# 16197_4.net
KiCad netlist of a schematic drawn in EAGLE
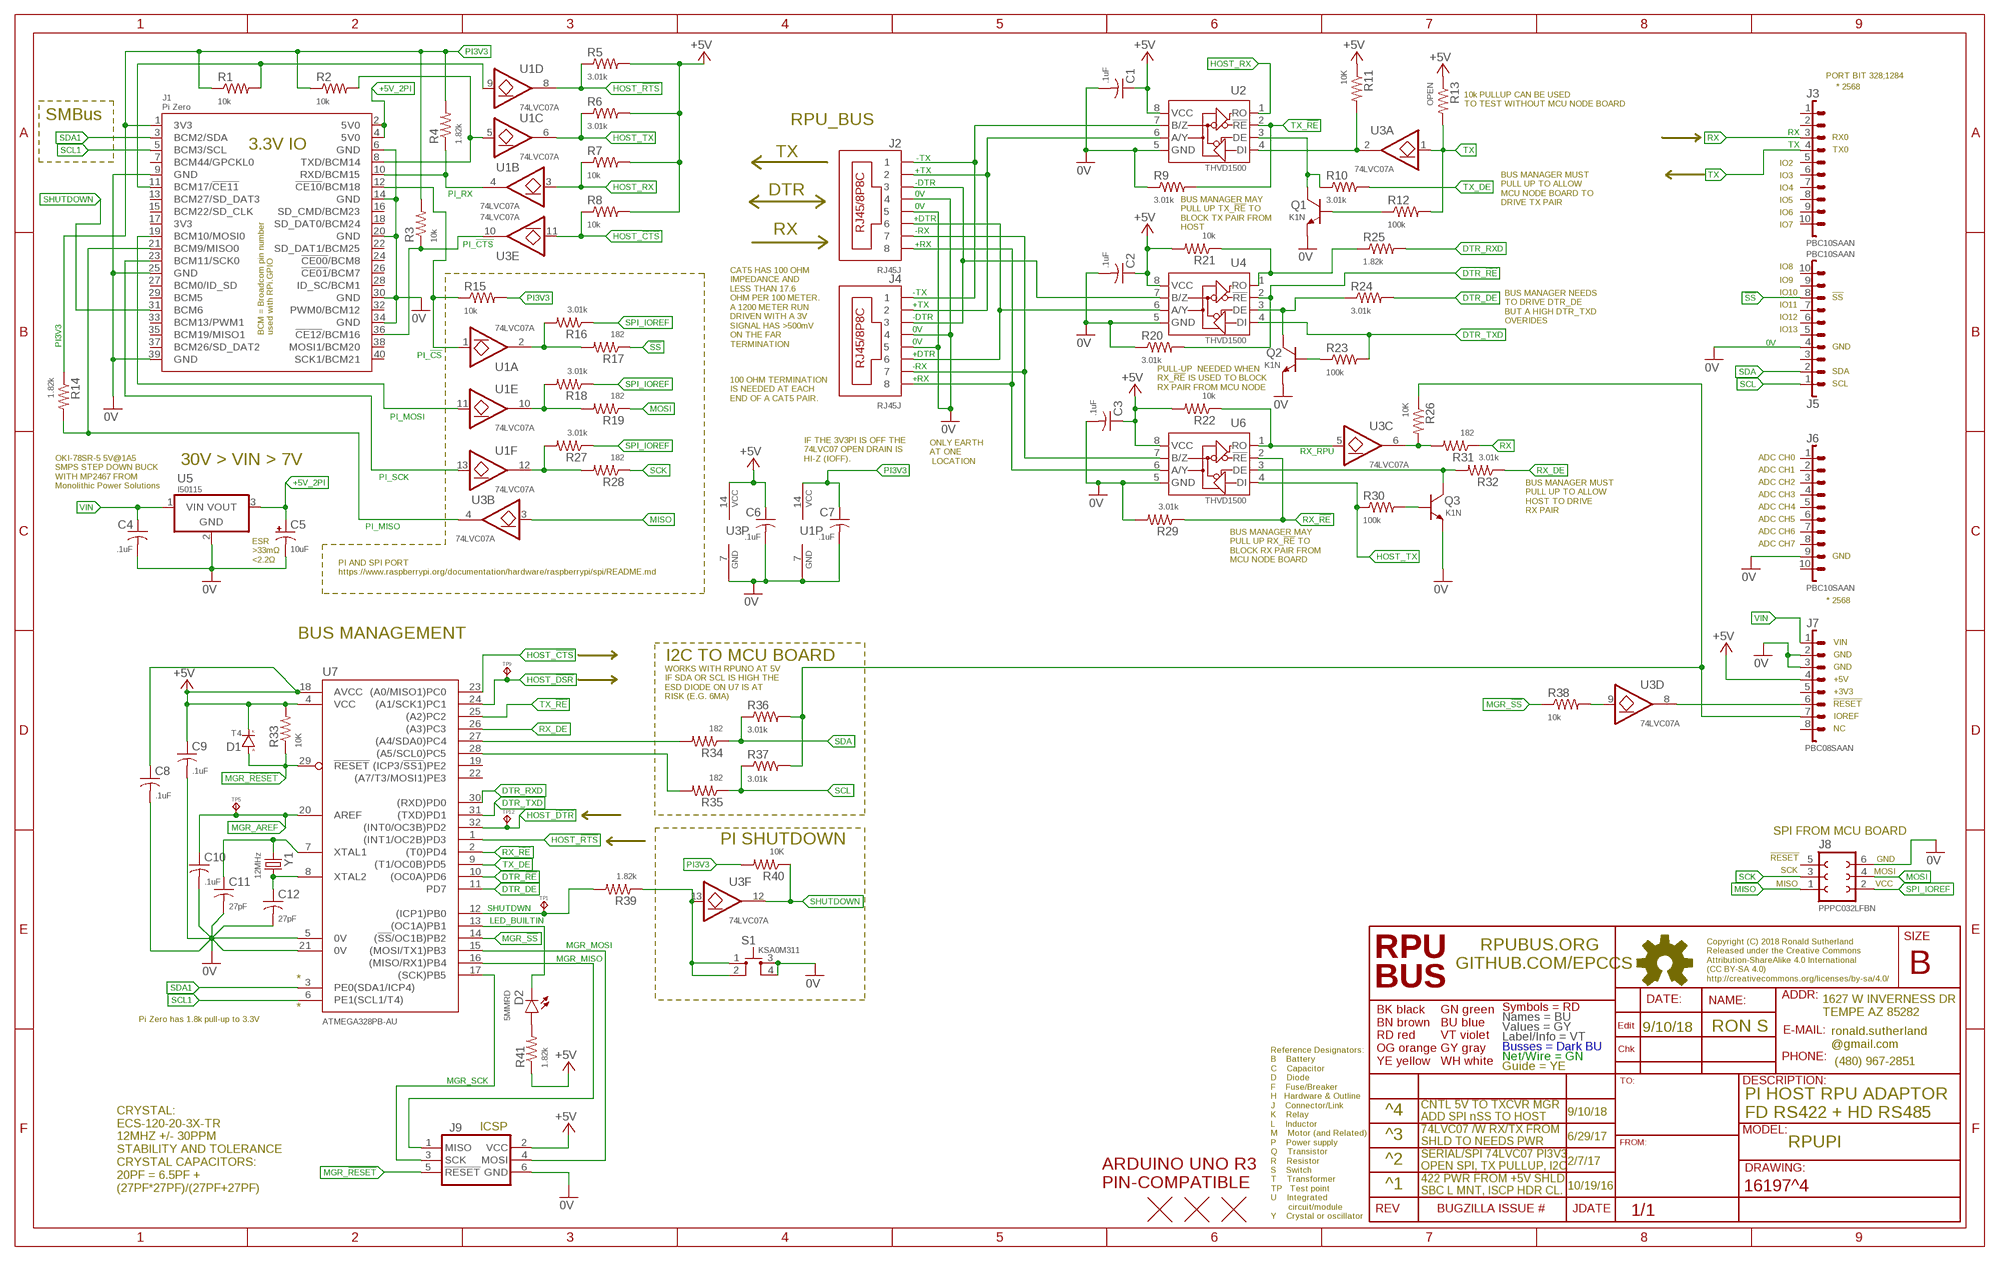
[diagram p0: schematic, sheet 1]

(export (version "E")
  (design (tool "Eeschema 10.0.6"))
  (components
    (comp (ref "C1")
      (value ".1uF")
      (footprint "eagle-import:C0603(1608)")
      (libsource (lib "eagle-import") (part "CC0603A"))
    )
    (comp (ref "C2")
      (value ".1uF")
      (footprint "eagle-import:C0603(1608)")
      (libsource (lib "eagle-import") (part "CC0603A"))
    )
    (comp (ref "C3")
      (value ".1uF")
      (footprint "eagle-import:C0603(1608)")
      (libsource (lib "eagle-import") (part "CC0603A"))
    )
    (comp (ref "C4")
      (value ".1uF")
      (footprint "eagle-import:C0603(1608)")
      (libsource (lib "eagle-import") (part "CC0603A"))
    )
    (comp (ref "C5")
      (value "10uF")
      (footprint "eagle-import:3216")
      (libsource (lib "eagle-import") (part "CT1206"))
    )
    (comp (ref "C6")
      (value ".1uF")
      (footprint "eagle-import:C0603(1608)")
      (libsource (lib "eagle-import") (part "CC0603A"))
    )
    (comp (ref "C7")
      (value ".1uF")
      (footprint "eagle-import:C0603(1608)")
      (libsource (lib "eagle-import") (part "CC0603A"))
    )
    (comp (ref "C8")
      (value ".1uF")
      (footprint "eagle-import:C0603(1608)")
      (libsource (lib "eagle-import") (part "CC0603A"))
    )
    (comp (ref "C9")
      (value ".1uF")
      (footprint "eagle-import:C0603(1608)")
      (libsource (lib "eagle-import") (part "CC0603A"))
    )
    (comp (ref "C10")
      (value ".1uF")
      (footprint "eagle-import:C0603(1608)")
      (libsource (lib "eagle-import") (part "CC0603A"))
    )
    (comp (ref "C11")
      (value "27pF")
      (footprint "eagle-import:C0603(1608)")
      (libsource (lib "eagle-import") (part "CC0603A"))
    )
    (comp (ref "C12")
      (value "27pF")
      (footprint "eagle-import:C0603(1608)")
      (libsource (lib "eagle-import") (part "CC0603A"))
    )
    (comp (ref "D1")
      (value "T4")
      (footprint "eagle-import:SOD123")
      (libsource (lib "eagle-import") (part "DSOD123"))
    )
    (comp (ref "D2")
      (value "5MMRD")
      (footprint "eagle-import:LED5MM")
      (libsource (lib "eagle-import") (part "LED5MM"))
    )
    (comp (ref "J1")
      (value "Pi Zero")
      (footprint "eagle-import:RASPI_ZERO_V40PIN")
      (libsource (lib "eagle-import") (part "RPI-ZERO90"))
    )
    (comp (ref "J2")
      (value "RJ45J")
      (footprint "eagle-import:RJ45-8HZT")
      (libsource (lib "eagle-import") (part "RJ45-8HZT"))
    )
    (comp (ref "J3")
      (value "PBC10SAAN")
      (footprint "eagle-import:1X10")
      (libsource (lib "eagle-import") (part "1X10{dblquote}"))
    )
    (comp (ref "J4")
      (value "RJ45J")
      (footprint "eagle-import:RJ45-8HZT")
      (libsource (lib "eagle-import") (part "RJ45-8HZT"))
    )
    (comp (ref "J5")
      (value "PBC10SAAN")
      (footprint "eagle-import:1X10")
      (libsource (lib "eagle-import") (part "1X10{dblquote}"))
    )
    (comp (ref "J6")
      (value "PBC10SAAN")
      (footprint "eagle-import:1X10")
      (libsource (lib "eagle-import") (part "1X10{dblquote}"))
    )
    (comp (ref "J7")
      (value "PBC08SAAN")
      (footprint "eagle-import:1X8")
      (libsource (lib "eagle-import") (part "1X8{dblquote}"))
    )
    (comp (ref "J8")
      (value "PPPC032LFBN")
      (footprint "eagle-import:F2X3")
      (libsource (lib "eagle-import") (part "F2X3"))
    )
    (comp (ref "J9")
      (value "ISP-SPIPTH")
      (footprint "eagle-import:ISP")
      (libsource (lib "eagle-import") (part "ISP-SPIPTH"))
    )
    (comp (ref "Q1")
      (value "K1N")
      (footprint "eagle-import:SOT23")
      (libsource (lib "eagle-import") (part "NPNSOT23"))
    )
    (comp (ref "Q2")
      (value "K1N")
      (footprint "eagle-import:SOT23")
      (libsource (lib "eagle-import") (part "NPNSOT23"))
    )
    (comp (ref "Q3")
      (value "K1N")
      (footprint "eagle-import:SOT23")
      (libsource (lib "eagle-import") (part "NPNSOT23"))
    )
    (comp (ref "R1")
      (value "10k")
      (footprint "eagle-import:C0805(2012)")
      (libsource (lib "eagle-import") (part "R0805"))
    )
    (comp (ref "R2")
      (value "10k")
      (footprint "eagle-import:C0805(2012)")
      (libsource (lib "eagle-import") (part "R0805"))
    )
    (comp (ref "R3")
      (value "10k")
      (footprint "eagle-import:C0805(2012)")
      (libsource (lib "eagle-import") (part "R0805"))
    )
    (comp (ref "R4")
      (value "1.82k")
      (footprint "eagle-import:C0805(2012)")
      (libsource (lib "eagle-import") (part "R0805"))
    )
    (comp (ref "R5")
      (value "3.01k")
      (footprint "eagle-import:C0805(2012)")
      (libsource (lib "eagle-import") (part "R0805"))
    )
    (comp (ref "R6")
      (value "3.01k")
      (footprint "eagle-import:C0805(2012)")
      (libsource (lib "eagle-import") (part "R0805"))
    )
    (comp (ref "R7")
      (value "10k")
      (footprint "eagle-import:C0805(2012)")
      (libsource (lib "eagle-import") (part "R0805"))
    )
    (comp (ref "R8")
      (value "10k")
      (footprint "eagle-import:C0805(2012)")
      (libsource (lib "eagle-import") (part "R0805"))
    )
    (comp (ref "R9")
      (value "3.01k")
      (footprint "eagle-import:C0805(2012)")
      (libsource (lib "eagle-import") (part "R0805"))
    )
    (comp (ref "R10")
      (value "3.01k")
      (footprint "eagle-import:C0805(2012)")
      (libsource (lib "eagle-import") (part "R0805"))
    )
    (comp (ref "R11")
      (value "10K")
      (footprint "eagle-import:C0805(2012)")
      (libsource (lib "eagle-import") (part "R0805"))
    )
    (comp (ref "R12")
      (value "100k")
      (footprint "eagle-import:C0805(2012)")
      (libsource (lib "eagle-import") (part "R0805"))
    )
    (comp (ref "R13")
      (value "OPEN")
      (footprint "eagle-import:C0805(2012)")
      (libsource (lib "eagle-import") (part "R0805"))
    )
    (comp (ref "R14")
      (value "1.82k")
      (footprint "eagle-import:C0805(2012)")
      (libsource (lib "eagle-import") (part "R0805"))
    )
    (comp (ref "R15")
      (value "10k")
      (footprint "eagle-import:C0805(2012)")
      (libsource (lib "eagle-import") (part "R0805"))
    )
    (comp (ref "R16")
      (value "3.01k")
      (footprint "eagle-import:C0805(2012)")
      (libsource (lib "eagle-import") (part "R0805"))
    )
    (comp (ref "R17")
      (value "182")
      (footprint "eagle-import:C0805(2012)")
      (libsource (lib "eagle-import") (part "R0805"))
    )
    (comp (ref "R18")
      (value "3.01k")
      (footprint "eagle-import:C0805(2012)")
      (libsource (lib "eagle-import") (part "R0805"))
    )
    (comp (ref "R19")
      (value "182")
      (footprint "eagle-import:C0805(2012)")
      (libsource (lib "eagle-import") (part "R0805"))
    )
    (comp (ref "R20")
      (value "3.01k")
      (footprint "eagle-import:C0805(2012)")
      (libsource (lib "eagle-import") (part "R0805"))
    )
    (comp (ref "R21")
      (value "10k")
      (footprint "eagle-import:C0805(2012)")
      (libsource (lib "eagle-import") (part "R0805"))
    )
    (comp (ref "R22")
      (value "10k")
      (footprint "eagle-import:C0805(2012)")
      (libsource (lib "eagle-import") (part "R0805"))
    )
    (comp (ref "R23")
      (value "100k")
      (footprint "eagle-import:C0805(2012)")
      (libsource (lib "eagle-import") (part "R0805"))
    )
    (comp (ref "R24")
      (value "3.01k")
      (footprint "eagle-import:C0805(2012)")
      (libsource (lib "eagle-import") (part "R0805"))
    )
    (comp (ref "R25")
      (value "1.82k")
      (footprint "eagle-import:C0805(2012)")
      (libsource (lib "eagle-import") (part "R0805"))
    )
    (comp (ref "R26")
      (value "10K")
      (footprint "eagle-import:C0805(2012)")
      (libsource (lib "eagle-import") (part "R0805"))
    )
    (comp (ref "R27")
      (value "3.01k")
      (footprint "eagle-import:C0805(2012)")
      (libsource (lib "eagle-import") (part "R0805"))
    )
    (comp (ref "R28")
      (value "182")
      (footprint "eagle-import:C0805(2012)")
      (libsource (lib "eagle-import") (part "R0805"))
    )
    (comp (ref "R29")
      (value "3.01k")
      (footprint "eagle-import:C0805(2012)")
      (libsource (lib "eagle-import") (part "R0805"))
    )
    (comp (ref "R30")
      (value "100k")
      (footprint "eagle-import:C0805(2012)")
      (libsource (lib "eagle-import") (part "R0805"))
    )
    (comp (ref "R31")
      (value "182")
      (footprint "eagle-import:C0805(2012)")
      (libsource (lib "eagle-import") (part "R0805"))
    )
    (comp (ref "R32")
      (value "3.01k")
      (footprint "eagle-import:C0805(2012)")
      (libsource (lib "eagle-import") (part "R0805"))
    )
    (comp (ref "R33")
      (value "10K")
      (footprint "eagle-import:C0805(2012)")
      (libsource (lib "eagle-import") (part "R0805"))
    )
    (comp (ref "R34")
      (value "182")
      (footprint "eagle-import:C0805(2012)")
      (libsource (lib "eagle-import") (part "R0805"))
    )
    (comp (ref "R35")
      (value "182")
      (footprint "eagle-import:C0805(2012)")
      (libsource (lib "eagle-import") (part "R0805"))
    )
    (comp (ref "R36")
      (value "3.01k")
      (footprint "eagle-import:C0805(2012)")
      (libsource (lib "eagle-import") (part "R0805"))
    )
    (comp (ref "R37")
      (value "3.01k")
      (footprint "eagle-import:C0805(2012)")
      (libsource (lib "eagle-import") (part "R0805"))
    )
    (comp (ref "R38")
      (value "10k")
      (footprint "eagle-import:C0805(2012)")
      (libsource (lib "eagle-import") (part "R0805"))
    )
    (comp (ref "R39")
      (value "1.82k")
      (footprint "eagle-import:C0805(2012)")
      (libsource (lib "eagle-import") (part "R0805"))
    )
    (comp (ref "R40")
      (value "10K")
      (footprint "eagle-import:C0805(2012)")
      (libsource (lib "eagle-import") (part "R0805"))
    )
    (comp (ref "R41")
      (value "1.82k")
      (footprint "eagle-import:C0805(2012)")
      (libsource (lib "eagle-import") (part "R0805"))
    )
    (comp (ref "S1")
      (value "KSA0M311")
      (footprint "eagle-import:0M311")
      (libsource (lib "eagle-import") (part "KSA0M311"))
    )
    (comp (ref "TP1")
      (value "TPPAD1-08")
      (footprint "eagle-import:P1-08")
      (libsource (lib "eagle-import") (part "TPPAD1-08"))
    )
    (comp (ref "TP5")
      (value "TPPAD1-08")
      (footprint "eagle-import:P1-08")
      (libsource (lib "eagle-import") (part "TPPAD1-08"))
    )
    (comp (ref "TP9")
      (value "TPPAD1-08")
      (footprint "eagle-import:P1-08")
      (libsource (lib "eagle-import") (part "TPPAD1-08"))
    )
    (comp (ref "TP12")
      (value "TPPAD1-08")
      (footprint "eagle-import:P1-08")
      (libsource (lib "eagle-import") (part "TPPAD1-08"))
    )
    (comp (ref "U$1")
      (value "ARDUINO-UNO")
      (footprint "eagle-import:ARDUINO_UNO")
      (libsource (lib "eagle-import") (part "ARDUINO-UNO"))
    )
    (comp (ref "U$2")
      (value "FIDUCIAL1.27")
      (footprint "eagle-import:FIDUCIAL-1.27")
      (libsource (lib "eagle-import") (part "FIDUCIAL1.27"))
    )
    (comp (ref "U$3")
      (value "FIDUCIAL1.27")
      (footprint "eagle-import:FIDUCIAL-1.27")
      (libsource (lib "eagle-import") (part "FIDUCIAL1.27"))
    )
    (comp (ref "U$4")
      (value "FIDUCIAL1.27")
      (footprint "eagle-import:FIDUCIAL-1.27")
      (libsource (lib "eagle-import") (part "FIDUCIAL1.27"))
    )
    (comp (ref "U1")
      (value "74LVC07A")
      (footprint "eagle-import:14SOIC")
      (libsource (lib "eagle-import") (part "7407D"))
    )
    (comp (ref "U2")
      (value "THVD1500")
      (footprint "eagle-import:SOIC8")
      (libsource (lib "eagle-import") (part "ISL3172EIBZ"))
    )
    (comp (ref "U3")
      (value "74LVC07A")
      (footprint "eagle-import:14SOIC")
      (libsource (lib "eagle-import") (part "7407D"))
    )
    (comp (ref "U4")
      (value "THVD1500")
      (footprint "eagle-import:SOIC8")
      (libsource (lib "eagle-import") (part "ISL3172EIBZ"))
    )
    (comp (ref "U5")
      (value "I50115")
      (footprint "eagle-import:OKI-78SR-H")
      (libsource (lib "eagle-import") (part "OKI-78SR-H"))
    )
    (comp (ref "U6")
      (value "THVD1500")
      (footprint "eagle-import:SOIC8")
      (libsource (lib "eagle-import") (part "ISL3172EIBZ"))
    )
    (comp (ref "U7")
      (value "ATMEGA328PB-AU")
      (footprint "eagle-import:TQFP32-08")
      (libsource (lib "eagle-import") (part "ATMEGA328PB-AU"))
    )
    (comp (ref "Y1")
      (value "12MHz")
      (footprint "eagle-import:CSM-3X")
      (libsource (lib "eagle-import") (part "CSM-3X"))
    )
  )
  (nets
    (net (code "1") (name "+5V") (class "Default")
      (node (ref "C1") (pin "1") (pinfunction "1_1") (pintype "passive"))
      (node (ref "C2") (pin "1") (pinfunction "1_1") (pintype "passive"))
      (node (ref "C3") (pin "1") (pinfunction "1_1") (pintype "passive"))
      (node (ref "C6") (pin "1") (pinfunction "1_1") (pintype "passive"))
      (node (ref "C8") (pin "1") (pinfunction "1_1") (pintype "passive"))
      (node (ref "C9") (pin "1") (pinfunction "1_1") (pintype "passive"))
      (node (ref "D1") (pin "C") (pinfunction "K_C") (pintype "passive"))
      (node (ref "J7") (pin "4") (pinfunction "4_4") (pintype "passive"))
      (node (ref "J9") (pin "2") (pinfunction "VCC_2") (pintype "bidirectional"))
      (node (ref "R11") (pin "1") (pinfunction "1_1") (pintype "passive"))
      (node (ref "R13") (pin "1") (pinfunction "1_1") (pintype "passive"))
      (node (ref "R21") (pin "2") (pinfunction "2_2") (pintype "passive"))
      (node (ref "R22") (pin "2") (pinfunction "2_2") (pintype "passive"))
      (node (ref "R33") (pin "2") (pinfunction "2_2") (pintype "passive"))
      (node (ref "R41") (pin "1") (pinfunction "1_1") (pintype "passive"))
      (node (ref "R5") (pin "2") (pinfunction "2_2") (pintype "passive"))
      (node (ref "R6") (pin "2") (pinfunction "2_2") (pintype "passive"))
      (node (ref "R7") (pin "2") (pinfunction "2_2") (pintype "passive"))
      (node (ref "R8") (pin "2") (pinfunction "2_2") (pintype "passive"))
      (node (ref "U2") (pin "8") (pinfunction "VCC_8") (pintype "power_in"))
      (node (ref "U3") (pin "14") (pinfunction "VCC_14") (pintype "power_in"))
      (node (ref "U4") (pin "8") (pinfunction "VCC_8") (pintype "power_in"))
      (node (ref "U6") (pin "8") (pinfunction "VCC_8") (pintype "power_in"))
      (node (ref "U7") (pin "18") (pinfunction "AVCC_18") (pintype "passive"))
      (node (ref "U7") (pin "4") (pinfunction "VCC_4") (pintype "power_in"))
    )
    (net (code "2") (name "+5V_2PI") (class "Default")
      (node (ref "C5") (pin "+") (pinfunction "+_+") (pintype "passive"))
      (node (ref "J1") (pin "2") (pinfunction "5V0_2") (pintype "power_in"))
      (node (ref "J1") (pin "4") (pinfunction "5V0_4") (pintype "power_in"))
      (node (ref "U5") (pin "3") (pinfunction "VOUT_3") (pintype "passive"))
    )
    (net (code "3") (name "/+DTR") (class "Default")
      (node (ref "J2") (pin "6") (pinfunction "6_6") (pintype "bidirectional"))
      (node (ref "J4") (pin "6") (pinfunction "6_6") (pintype "bidirectional"))
      (node (ref "U4") (pin "6") (pinfunction "A/Y_6") (pintype "bidirectional"))
    )
    (net (code "4") (name "/+RX") (class "Default")
      (node (ref "J2") (pin "8") (pinfunction "8_8") (pintype "bidirectional"))
      (node (ref "J4") (pin "8") (pinfunction "8_8") (pintype "bidirectional"))
      (node (ref "U6") (pin "6") (pinfunction "A/Y_6") (pintype "bidirectional"))
    )
    (net (code "5") (name "/+TX") (class "Default")
      (node (ref "J2") (pin "2") (pinfunction "2_2") (pintype "bidirectional"))
      (node (ref "J4") (pin "2") (pinfunction "2_2") (pintype "bidirectional"))
      (node (ref "U2") (pin "6") (pinfunction "A/Y_6") (pintype "bidirectional"))
    )
    (net (code "6") (name "/-DTR") (class "Default")
      (node (ref "J2") (pin "3") (pinfunction "3_3") (pintype "bidirectional"))
      (node (ref "J4") (pin "3") (pinfunction "3_3") (pintype "bidirectional"))
      (node (ref "U4") (pin "7") (pinfunction "B/Z_7") (pintype "bidirectional"))
    )
    (net (code "7") (name "/-RX") (class "Default")
      (node (ref "J2") (pin "7") (pinfunction "7_7") (pintype "bidirectional"))
      (node (ref "J4") (pin "7") (pinfunction "7_7") (pintype "bidirectional"))
      (node (ref "U6") (pin "7") (pinfunction "B/Z_7") (pintype "bidirectional"))
    )
    (net (code "8") (name "/-TX") (class "Default")
      (node (ref "J2") (pin "1") (pinfunction "1_1") (pintype "bidirectional"))
      (node (ref "J4") (pin "1") (pinfunction "1_1") (pintype "bidirectional"))
      (node (ref "U2") (pin "7") (pinfunction "B/Z_7") (pintype "bidirectional"))
    )
    (net (code "9") (name "/3V3") (class "Default")
      (node (ref "J1") (pin "17") (pinfunction "3V3_17") (pintype "power_in"))
    )
    (net (code "10") (name "/DTR_~{RE}") (class "Default")
      (node (ref "R20") (pin "2") (pinfunction "2_2") (pintype "passive"))
      (node (ref "U4") (pin "2") (pinfunction "~{RE}_2") (pintype "input"))
      (node (ref "U7") (pin "10") (pinfunction "(OC0A)PD6_10") (pintype "bidirectional"))
    )
    (net (code "11") (name "/HOST_~{CTS}") (class "Default")
      (node (ref "R8") (pin "1") (pinfunction "1_1") (pintype "passive"))
      (node (ref "U3") (pin "11") (pinfunction "I_11") (pintype "input"))
      (node (ref "U7") (pin "23") (pinfunction "(A0/MISO1)PC0_23") (pintype "bidirectional"))
    )
    (net (code "12") (name "/HOST_~{DSR}") (class "Default")
      (node (ref "TP9") (pin "TP") (pinfunction "TP_TP") (pintype "input"))
      (node (ref "U7") (pin "24") (pinfunction "(A1/SCK1)PC1_24") (pintype "bidirectional"))
    )
    (net (code "13") (name "/HOST_~{DTR}") (class "Default")
      (node (ref "TP12") (pin "TP") (pinfunction "TP_TP") (pintype "input"))
      (node (ref "U7") (pin "32") (pinfunction "(INT0/OC3B)PD2_32") (pintype "bidirectional"))
    )
    (net (code "14") (name "/HOST_~{RTS}") (class "Default")
      (node (ref "R5") (pin "1") (pinfunction "1_1") (pintype "passive"))
      (node (ref "U1") (pin "8") (pinfunction "O_8") (pintype "open_collector"))
      (node (ref "U7") (pin "1") (pinfunction "(INT1/OC2B)PD3_1") (pintype "bidirectional"))
    )
    (net (code "15") (name "/LED_BUILTIN") (class "Default")
      (node (ref "D2") (pin "K") (pinfunction "K_K") (pintype "passive"))
      (node (ref "U7") (pin "13") (pinfunction "(OC1A)PB1_13") (pintype "bidirectional"))
    )
    (net (code "16") (name "/MGR_MISO") (class "Default")
      (node (ref "J9") (pin "1") (pinfunction "MISO_1") (pintype "bidirectional"))
      (node (ref "U7") (pin "16") (pinfunction "(MISO/RX1)PB4_16") (pintype "bidirectional"))
    )
    (net (code "17") (name "/MGR_MOSI") (class "Default")
      (node (ref "J9") (pin "4") (pinfunction "MOSI_4") (pintype "bidirectional"))
      (node (ref "U7") (pin "15") (pinfunction "(MOSI/TX1)PB3_15") (pintype "bidirectional"))
    )
    (net (code "18") (name "/MGR_SCK") (class "Default")
      (node (ref "J9") (pin "3") (pinfunction "SCK_3") (pintype "bidirectional"))
      (node (ref "U7") (pin "17") (pinfunction "(SCK)PB5_17") (pintype "bidirectional"))
    )
    (net (code "19") (name "/MGR_~{RESET}") (class "Default")
      (node (ref "D1") (pin "A") (pinfunction "A_A") (pintype "passive"))
      (node (ref "J9") (pin "5") (pinfunction "~{RESET}_5") (pintype "bidirectional"))
      (node (ref "R33") (pin "1") (pinfunction "1_1") (pintype "passive"))
      (node (ref "U7") (pin "29") (pinfunction "~{RESET}_29") (pintype "input"))
    )
    (net (code "20") (name "/MGR_~{SS}") (class "Default")
      (node (ref "R38") (pin "1") (pinfunction "1_1") (pintype "passive"))
      (node (ref "U7") (pin "14") (pinfunction "(~{SS}/OC1B)PB2_14") (pintype "bidirectional"))
    )
    (net (code "21") (name "/PI_MISO") (class "Default")
      (node (ref "J1") (pin "21") (pinfunction "BCM9/MISO0_21") (pintype "bidirectional"))
      (node (ref "R14") (pin "2") (pinfunction "2_2") (pintype "passive"))
      (node (ref "U3") (pin "4") (pinfunction "O_4") (pintype "open_collector"))
    )
    (net (code "22") (name "/PI_MOSI") (class "Default")
      (node (ref "J1") (pin "19") (pinfunction "BCM10/MOSI0_19") (pintype "bidirectional"))
      (node (ref "U1") (pin "11") (pinfunction "I_11") (pintype "input"))
    )
    (net (code "23") (name "/PI_RX") (class "Default")
      (node (ref "J1") (pin "10") (pinfunction "RXD/BCM15_10") (pintype "bidirectional"))
      (node (ref "R4") (pin "1") (pinfunction "1_1") (pintype "passive"))
      (node (ref "U1") (pin "4") (pinfunction "O_4") (pintype "open_collector"))
    )
    (net (code "24") (name "/PI_SCK") (class "Default")
      (node (ref "J1") (pin "23") (pinfunction "BCM11/SCK0_23") (pintype "bidirectional"))
      (node (ref "U1") (pin "13") (pinfunction "I_13") (pintype "input"))
    )
    (net (code "25") (name "/PI_~{CS}") (class "Default")
      (node (ref "J1") (pin "12") (pinfunction "~{CE10}/BCM18_12") (pintype "bidirectional"))
      (node (ref "R15") (pin "1") (pinfunction "1_1") (pintype "passive"))
      (node (ref "U1") (pin "1") (pinfunction "I_1") (pintype "input"))
    )
    (net (code "26") (name "/PI_~{CTS}") (class "Default")
      (node (ref "J1") (pin "36") (pinfunction "~{CE12}/BCM16_36") (pintype "bidirectional"))
      (node (ref "R3") (pin "1") (pinfunction "1_1") (pintype "passive"))
      (node (ref "U3") (pin "10") (pinfunction "O_10") (pintype "open_collector"))
    )
    (net (code "27") (name "/RX_RPU") (class "Default")
      (node (ref "R22") (pin "1") (pinfunction "1_1") (pintype "passive"))
      (node (ref "U3") (pin "5") (pinfunction "I_5") (pintype "input"))
      (node (ref "U6") (pin "1") (pinfunction "RO_1") (pintype "output"))
    )
    (net (code "28") (name "/RX_~{RE}") (class "Default")
      (node (ref "R29") (pin "1") (pinfunction "1_1") (pintype "passive"))
      (node (ref "U6") (pin "2") (pinfunction "~{RE}_2") (pintype "input"))
      (node (ref "U7") (pin "2") (pinfunction "(T0)PD4_2") (pintype "bidirectional"))
    )
    (net (code "29") (name "/SHUTDWN") (class "Default")
      (node (ref "R39") (pin "2") (pinfunction "2_2") (pintype "passive"))
      (node (ref "TP1") (pin "TP") (pinfunction "TP_TP") (pintype "input"))
      (node (ref "U7") (pin "12") (pinfunction "(ICP1)PB0_12") (pintype "bidirectional"))
    )
    (net (code "30") (name "/TX_~{RE}") (class "Default")
      (node (ref "R9") (pin "2") (pinfunction "2_2") (pintype "passive"))
      (node (ref "U2") (pin "2") (pinfunction "~{RE}_2") (pintype "input"))
      (node (ref "U7") (pin "25") (pinfunction "(A2)PC2_25") (pintype "bidirectional"))
    )
    (net (code "31") (name "/~{SS}") (class "Default")
      (node (ref "J5") (pin "8") (pinfunction "8_8") (pintype "passive"))
      (node (ref "R17") (pin "1") (pinfunction "1_1") (pintype "passive"))
    )
    (net (code "32") (name "0V") (class "Default")
      (node (ref "C1") (pin "2") (pinfunction "2_2") (pintype "passive"))
      (node (ref "C10") (pin "2") (pinfunction "2_2") (pintype "passive"))
      (node (ref "C11") (pin "2") (pinfunction "2_2") (pintype "passive"))
      (node (ref "C12") (pin "2") (pinfunction "2_2") (pintype "passive"))
      (node (ref "C2") (pin "2") (pinfunction "2_2") (pintype "passive"))
      (node (ref "C3") (pin "2") (pinfunction "2_2") (pintype "passive"))
      (node (ref "C4") (pin "2") (pinfunction "2_2") (pintype "passive"))
      (node (ref "C5") (pin "-") (pinfunction "-_-") (pintype "passive"))
      (node (ref "C6") (pin "2") (pinfunction "2_2") (pintype "passive"))
      (node (ref "C7") (pin "2") (pinfunction "2_2") (pintype "passive"))
      (node (ref "C8") (pin "2") (pinfunction "2_2") (pintype "passive"))
      (node (ref "C9") (pin "2") (pinfunction "2_2") (pintype "passive"))
      (node (ref "J1") (pin "14") (pinfunction "GND_14") (pintype "power_in"))
      (node (ref "J1") (pin "20") (pinfunction "GND_20") (pintype "power_in"))
      (node (ref "J1") (pin "25") (pinfunction "GND_25") (pintype "power_in"))
      (node (ref "J1") (pin "30") (pinfunction "GND_30") (pintype "power_in"))
      (node (ref "J1") (pin "34") (pinfunction "GND_34") (pintype "power_in"))
      (node (ref "J1") (pin "39") (pinfunction "GND_39") (pintype "power_in"))
      (node (ref "J1") (pin "6") (pinfunction "GND_6") (pintype "power_in"))
      (node (ref "J1") (pin "9") (pinfunction "GND_9") (pintype "power_in"))
      (node (ref "J2") (pin "4") (pinfunction "4_4") (pintype "bidirectional"))
      (node (ref "J2") (pin "5") (pinfunction "5_5") (pintype "bidirectional"))
      (node (ref "J4") (pin "4") (pinfunction "4_4") (pintype "bidirectional"))
      (node (ref "J4") (pin "5") (pinfunction "5_5") (pintype "bidirectional"))
      (node (ref "J5") (pin "4") (pinfunction "4_4") (pintype "passive"))
      (node (ref "J6") (pin "9") (pinfunction "9_9") (pintype "passive"))
      (node (ref "J7") (pin "2") (pinfunction "2_2") (pintype "passive"))
      (node (ref "J7") (pin "3") (pinfunction "3_3") (pintype "passive"))
      (node (ref "J8") (pin "6") (pinfunction "6_6") (pintype "passive"))
      (node (ref "J9") (pin "6") (pinfunction "GND_6") (pintype "bidirectional"))
      (node (ref "Q1") (pin "E") (pinfunction "E_E") (pintype "passive"))
      (node (ref "Q2") (pin "E") (pinfunction "E_E") (pintype "passive"))
      (node (ref "Q3") (pin "E") (pinfunction "E_E") (pintype "passive"))
      (node (ref "R20") (pin "1") (pinfunction "1_1") (pintype "passive"))
      (node (ref "R29") (pin "2") (pinfunction "2_2") (pintype "passive"))
      (node (ref "R9") (pin "1") (pinfunction "1_1") (pintype "passive"))
      (node (ref "S1") (pin "3") (pinfunction "3_3") (pintype "passive"))
      (node (ref "S1") (pin "4") (pinfunction "4_4") (pintype "passive"))
      (node (ref "U1") (pin "7") (pinfunction "GND_7") (pintype "power_in"))
      (node (ref "U2") (pin "5") (pinfunction "GND_5") (pintype "power_in"))
      (node (ref "U3") (pin "7") (pinfunction "GND_7") (pintype "power_in"))
      (node (ref "U4") (pin "5") (pinfunction "GND_5") (pintype "power_in"))
      (node (ref "U5") (pin "2") (pinfunction "GND_2") (pintype "passive"))
      (node (ref "U6") (pin "5") (pinfunction "GND_5") (pintype "power_in"))
      (node (ref "U7") (pin "21") (pinfunction "0V_21") (pintype "power_in"))
      (node (ref "U7") (pin "5") (pinfunction "0V_5") (pintype "power_in"))
    )
    (net (code "33") (name "DTR_DE") (class "Default")
      (node (ref "R24") (pin "2") (pinfunction "2_2") (pintype "passive"))
      (node (ref "U7") (pin "11") (pinfunction "PD7_11") (pintype "bidirectional"))
    )
    (net (code "34") (name "DTR_RXD") (class "Default")
      (node (ref "R25") (pin "2") (pinfunction "2_2") (pintype "passive"))
      (node (ref "U7") (pin "30") (pinfunction "(RXD)PD0_30") (pintype "bidirectional"))
    )
    (net (code "35") (name "DTR_TXD") (class "Default")
      (node (ref "R23") (pin "2") (pinfunction "2_2") (pintype "passive"))
      (node (ref "U4") (pin "4") (pinfunction "DI_4") (pintype "input"))
      (node (ref "U7") (pin "31") (pinfunction "(TXD)PD1_31") (pintype "bidirectional"))
    )
    (net (code "36") (name "HOST_RX") (class "Default")
      (node (ref "R7") (pin "1") (pinfunction "1_1") (pintype "passive"))
      (node (ref "U1") (pin "3") (pinfunction "I_3") (pintype "input"))
      (node (ref "U2") (pin "1") (pinfunction "RO_1") (pintype "output"))
    )
    (net (code "37") (name "HOST_TX") (class "Default")
      (node (ref "R30") (pin "1") (pinfunction "1_1") (pintype "passive"))
      (node (ref "R6") (pin "1") (pinfunction "1_1") (pintype "passive"))
      (node (ref "U1") (pin "6") (pinfunction "O_6") (pintype "open_collector"))
      (node (ref "U6") (pin "4") (pinfunction "DI_4") (pintype "input"))
    )
    (net (code "38") (name "MGR_AREF") (class "Default")
      (node (ref "C10") (pin "1") (pinfunction "1_1") (pintype "passive"))
      (node (ref "TP5") (pin "TP") (pinfunction "TP_TP") (pintype "input"))
      (node (ref "U7") (pin "20") (pinfunction "AREF_20") (pintype "passive"))
    )
    (net (code "39") (name "MISO") (class "Default")
      (node (ref "J8") (pin "1") (pinfunction "1_1") (pintype "passive"))
      (node (ref "U3") (pin "3") (pinfunction "I_3") (pintype "input"))
    )
    (net (code "40") (name "MOSI") (class "Default")
      (node (ref "J8") (pin "4") (pinfunction "4_4") (pintype "passive"))
      (node (ref "R19") (pin "1") (pinfunction "1_1") (pintype "passive"))
    )
    (net (code "41") (name "Net-(D2-PadA)") (class "Default")
      (node (ref "D2") (pin "A") (pinfunction "A_A") (pintype "passive"))
      (node (ref "R41") (pin "2") (pinfunction "2_2") (pintype "passive"))
    )
    (net (code "42") (name "Net-(J1-BCM17{slash}~{CE11})") (class "Default")
      (node (ref "J1") (pin "11") (pinfunction "BCM17/~{CE11}_11") (pintype "bidirectional"))
      (node (ref "R1") (pin "2") (pinfunction "2_2") (pintype "passive"))
      (node (ref "U1") (pin "9") (pinfunction "I_9") (pintype "input"))
    )
    (net (code "43") (name "Net-(J1-TXD{slash}BCM14)") (class "Default")
      (node (ref "J1") (pin "8") (pinfunction "TXD/BCM14_8") (pintype "bidirectional"))
      (node (ref "R2") (pin "2") (pinfunction "2_2") (pintype "passive"))
      (node (ref "U1") (pin "5") (pinfunction "I_5") (pintype "input"))
    )
    (net (code "44") (name "Net-(J7-Pad7)") (class "Default")
      (node (ref "J7") (pin "7") (pinfunction "7_7") (pintype "passive"))
      (node (ref "R26") (pin "1") (pinfunction "1_1") (pintype "passive"))
      (node (ref "R36") (pin "2") (pinfunction "2_2") (pintype "passive"))
      (node (ref "R37") (pin "2") (pinfunction "2_2") (pintype "passive"))
    )
    (net (code "45") (name "Net-(Q1-PadB)") (class "Default")
      (node (ref "Q1") (pin "B") (pinfunction "B_B") (pintype "passive"))
      (node (ref "R12") (pin "1") (pinfunction "1_1") (pintype "passive"))
    )
    (net (code "46") (name "Net-(Q2-PadB)") (class "Default")
      (node (ref "Q2") (pin "B") (pinfunction "B_B") (pintype "passive"))
      (node (ref "R23") (pin "1") (pinfunction "1_1") (pintype "passive"))
    )
    (net (code "47") (name "Net-(Q3-PadB)") (class "Default")
      (node (ref "Q3") (pin "B") (pinfunction "B_B") (pintype "passive"))
      (node (ref "R30") (pin "2") (pinfunction "2_2") (pintype "passive"))
    )
    (net (code "48") (name "Net-(U1A-O)") (class "Default")
      (node (ref "R16") (pin "2") (pinfunction "2_2") (pintype "passive"))
      (node (ref "R17") (pin "2") (pinfunction "2_2") (pintype "passive"))
      (node (ref "U1") (pin "2") (pinfunction "O_2") (pintype "open_collector"))
    )
    (net (code "49") (name "Net-(U1E-O)") (class "Default")
      (node (ref "R18") (pin "2") (pinfunction "2_2") (pintype "passive"))
      (node (ref "R19") (pin "2") (pinfunction "2_2") (pintype "passive"))
      (node (ref "U1") (pin "10") (pinfunction "O_10") (pintype "open_collector"))
    )
    (net (code "50") (name "Net-(U1F-O)") (class "Default")
      (node (ref "R27") (pin "2") (pinfunction "2_2") (pintype "passive"))
      (node (ref "R28") (pin "2") (pinfunction "2_2") (pintype "passive"))
      (node (ref "U1") (pin "12") (pinfunction "O_12") (pintype "open_collector"))
    )
    (net (code "51") (name "Net-(U2-DE)") (class "Default")
      (node (ref "Q1") (pin "C") (pinfunction "C_C") (pintype "passive"))
      (node (ref "R10") (pin "1") (pinfunction "1_1") (pintype "passive"))
      (node (ref "U2") (pin "3") (pinfunction "DE_3") (pintype "input"))
    )
    (net (code "52") (name "Net-(U2-DI)") (class "Default")
      (node (ref "R11") (pin "2") (pinfunction "2_2") (pintype "passive"))
      (node (ref "U2") (pin "4") (pinfunction "DI_4") (pintype "input"))
      (node (ref "U3") (pin "2") (pinfunction "O_2") (pintype "open_collector"))
    )
    (net (code "53") (name "Net-(U3C-O)") (class "Default")
      (node (ref "R26") (pin "2") (pinfunction "2_2") (pintype "passive"))
      (node (ref "R31") (pin "2") (pinfunction "2_2") (pintype "passive"))
      (node (ref "U3") (pin "6") (pinfunction "O_6") (pintype "open_collector"))
    )
    (net (code "54") (name "Net-(U3D-I)") (class "Default")
      (node (ref "R38") (pin "2") (pinfunction "2_2") (pintype "passive"))
      (node (ref "U3") (pin "9") (pinfunction "I_9") (pintype "input"))
    )
    (net (code "55") (name "Net-(U3D-O)") (class "Default")
      (node (ref "J7") (pin "6") (pinfunction "6_6") (pintype "passive"))
      (node (ref "U3") (pin "8") (pinfunction "O_8") (pintype "open_collector"))
    )
    (net (code "56") (name "Net-(U3F-I)") (class "Default")
      (node (ref "R39") (pin "1") (pinfunction "1_1") (pintype "passive"))
      (node (ref "S1") (pin "1") (pinfunction "1_1") (pintype "passive"))
      (node (ref "S1") (pin "2") (pinfunction "2_2") (pintype "passive"))
      (node (ref "U3") (pin "13") (pinfunction "I_13") (pintype "input"))
    )
    (net (code "57") (name "Net-(U4-DE)") (class "Default")
      (node (ref "Q2") (pin "C") (pinfunction "C_C") (pintype "passive"))
      (node (ref "R24") (pin "1") (pinfunction "1_1") (pintype "passive"))
      (node (ref "U4") (pin "3") (pinfunction "DE_3") (pintype "input"))
    )
    (net (code "58") (name "Net-(U4-RO)") (class "Default")
      (node (ref "R21") (pin "1") (pinfunction "1_1") (pintype "passive"))
      (node (ref "R25") (pin "1") (pinfunction "1_1") (pintype "passive"))
      (node (ref "U4") (pin "1") (pinfunction "RO_1") (pintype "output"))
    )
    (net (code "59") (name "Net-(U6-DE)") (class "Default")
      (node (ref "Q3") (pin "C") (pinfunction "C_C") (pintype "passive"))
      (node (ref "R32") (pin "2") (pinfunction "2_2") (pintype "passive"))
      (node (ref "U6") (pin "3") (pinfunction "DE_3") (pintype "input"))
    )
    (net (code "60") (name "Net-(U7-(A4{slash}SDA0)PC4)") (class "Default")
      (node (ref "R34") (pin "2") (pinfunction "2_2") (pintype "passive"))
      (node (ref "U7") (pin "27") (pinfunction "(A4/SDA0)PC4_27") (pintype "bidirectional"))
    )
    (net (code "61") (name "Net-(U7-(A5{slash}SCL0)PC5)") (class "Default")
      (node (ref "R35") (pin "2") (pinfunction "2_2") (pintype "passive"))
      (node (ref "U7") (pin "28") (pinfunction "(A5/SCL0)PC5_28") (pintype "bidirectional"))
    )
    (net (code "62") (name "Net-(U7-XTAL1)") (class "Default")
      (node (ref "C11") (pin "1") (pinfunction "1_1") (pintype "passive"))
      (node (ref "U7") (pin "7") (pinfunction "XTAL1_7") (pintype "bidirectional"))
      (node (ref "Y1") (pin "1") (pinfunction "1_1") (pintype "bidirectional"))
    )
    (net (code "63") (name "Net-(U7-XTAL2)") (class "Default")
      (node (ref "C12") (pin "1") (pinfunction "1_1") (pintype "passive"))
      (node (ref "U7") (pin "8") (pinfunction "XTAL2_8") (pintype "bidirectional"))
      (node (ref "Y1") (pin "2") (pinfunction "2_2") (pintype "bidirectional"))
    )
    (net (code "64") (name "PI3V3") (class "Default")
      (node (ref "C7") (pin "1") (pinfunction "1_1") (pintype "passive"))
      (node (ref "J1") (pin "1") (pinfunction "3V3_1") (pintype "power_in"))
      (node (ref "R1") (pin "1") (pinfunction "1_1") (pintype "passive"))
      (node (ref "R14") (pin "1") (pinfunction "1_1") (pintype "passive"))
      (node (ref "R15") (pin "2") (pinfunction "2_2") (pintype "passive"))
      (node (ref "R2") (pin "1") (pinfunction "1_1") (pintype "passive"))
      (node (ref "R3") (pin "2") (pinfunction "2_2") (pintype "passive"))
      (node (ref "R4") (pin "2") (pinfunction "2_2") (pintype "passive"))
      (node (ref "R40") (pin "2") (pinfunction "2_2") (pintype "passive"))
      (node (ref "U1") (pin "14") (pinfunction "VCC_14") (pintype "power_in"))
    )
    (net (code "65") (name "RX") (class "Default")
      (node (ref "J3") (pin "3") (pinfunction "3_3") (pintype "passive"))
      (node (ref "R31") (pin "1") (pinfunction "1_1") (pintype "passive"))
    )
    (net (code "66") (name "RX_DE") (class "Default")
      (node (ref "R32") (pin "1") (pinfunction "1_1") (pintype "passive"))
      (node (ref "U7") (pin "26") (pinfunction "(A3)PC3_26") (pintype "bidirectional"))
    )
    (net (code "67") (name "SCK") (class "Default")
      (node (ref "J8") (pin "3") (pinfunction "3_3") (pintype "passive"))
      (node (ref "R28") (pin "1") (pinfunction "1_1") (pintype "passive"))
    )
    (net (code "68") (name "SCL") (class "Default")
      (node (ref "J5") (pin "1") (pinfunction "1_1") (pintype "passive"))
      (node (ref "R35") (pin "1") (pinfunction "1_1") (pintype "passive"))
      (node (ref "R37") (pin "1") (pinfunction "1_1") (pintype "passive"))
    )
    (net (code "69") (name "SCL1") (class "Default")
      (node (ref "J1") (pin "5") (pinfunction "BCM3/SCL_5") (pintype "bidirectional"))
      (node (ref "U7") (pin "6") (pinfunction "PE1(SCL1/T4)_6") (pintype "bidirectional"))
    )
    (net (code "70") (name "SDA") (class "Default")
      (node (ref "J5") (pin "2") (pinfunction "2_2") (pintype "passive"))
      (node (ref "R34") (pin "1") (pinfunction "1_1") (pintype "passive"))
      (node (ref "R36") (pin "1") (pinfunction "1_1") (pintype "passive"))
    )
    (net (code "71") (name "SDA1") (class "Default")
      (node (ref "J1") (pin "3") (pinfunction "BCM2/SDA_3") (pintype "bidirectional"))
      (node (ref "U7") (pin "3") (pinfunction "PE0(SDA1/ICP4)_3") (pintype "bidirectional"))
    )
    (net (code "72") (name "SHUTDOWN") (class "Default")
      (node (ref "J1") (pin "31") (pinfunction "BCM6_31") (pintype "bidirectional"))
      (node (ref "R40") (pin "1") (pinfunction "1_1") (pintype "passive"))
      (node (ref "U3") (pin "12") (pinfunction "O_12") (pintype "open_collector"))
    )
    (net (code "73") (name "SPI_IOREF") (class "Default")
      (node (ref "J8") (pin "2") (pinfunction "2_2") (pintype "passive"))
      (node (ref "R16") (pin "1") (pinfunction "1_1") (pintype "passive"))
      (node (ref "R18") (pin "1") (pinfunction "1_1") (pintype "passive"))
      (node (ref "R27") (pin "1") (pinfunction "1_1") (pintype "passive"))
    )
    (net (code "74") (name "TX") (class "Default")
      (node (ref "J3") (pin "4") (pinfunction "4_4") (pintype "passive"))
      (node (ref "R12") (pin "2") (pinfunction "2_2") (pintype "passive"))
      (node (ref "R13") (pin "2") (pinfunction "2_2") (pintype "passive"))
      (node (ref "U3") (pin "1") (pinfunction "I_1") (pintype "input"))
    )
    (net (code "75") (name "TX_DE") (class "Default")
      (node (ref "R10") (pin "2") (pinfunction "2_2") (pintype "passive"))
      (node (ref "U7") (pin "9") (pinfunction "(T1/OC0B)PD5_9") (pintype "bidirectional"))
    )
    (net (code "76") (name "VIN") (class "Default")
      (node (ref "C4") (pin "1") (pinfunction "1_1") (pintype "passive"))
      (node (ref "J7") (pin "1") (pinfunction "1_1") (pintype "passive"))
      (node (ref "U5") (pin "1") (pinfunction "VIN_1") (pintype "passive"))
    )
    (net (code "77") (name "unconnected-(J1-BCM0{slash}ID_SD-Pad27)") (class "Default")
      (node (ref "J1") (pin "27") (pinfunction "BCM0/ID_SD_27") (pintype "bidirectional"))
    )
    (net (code "78") (name "unconnected-(J1-BCM5-Pad29)") (class "Default")
      (node (ref "J1") (pin "29") (pinfunction "BCM5_29") (pintype "bidirectional"))
    )
    (net (code "79") (name "unconnected-(J1-BCM13{slash}PWM1-Pad33)") (class "Default")
      (node (ref "J1") (pin "33") (pinfunction "BCM13/PWM1_33") (pintype "bidirectional"))
    )
    (net (code "80") (name "unconnected-(J1-BCM19{slash}MISO1-Pad35)") (class "Default")
      (node (ref "J1") (pin "35") (pinfunction "BCM19/MISO1_35") (pintype "bidirectional"))
    )
    (net (code "81") (name "unconnected-(J1-BCM22{slash}SD_CLK-Pad15)") (class "Default")
      (node (ref "J1") (pin "15") (pinfunction "BCM22/SD_CLK_15") (pintype "bidirectional"))
    )
    (net (code "82") (name "unconnected-(J1-BCM26{slash}SD_DAT2-Pad37)") (class "Default")
      (node (ref "J1") (pin "37") (pinfunction "BCM26/SD_DAT2_37") (pintype "bidirectional"))
    )
    (net (code "83") (name "unconnected-(J1-BCM27{slash}SD_DAT3-Pad13)") (class "Default")
      (node (ref "J1") (pin "13") (pinfunction "BCM27/SD_DAT3_13") (pintype "bidirectional"))
    )
    (net (code "84") (name "unconnected-(J1-BCM44{slash}GPCKL0-Pad7)") (class "Default")
      (node (ref "J1") (pin "7") (pinfunction "BCM44/GPCKL0_7") (pintype "bidirectional"))
    )
    (net (code "85") (name "unconnected-(J1-ID_SC{slash}BCM1-Pad28)") (class "Default")
      (node (ref "J1") (pin "28") (pinfunction "ID_SC/BCM1_28") (pintype "bidirectional"))
    )
    (net (code "86") (name "unconnected-(J1-MOSI1{slash}BCM20-Pad38)") (class "Default")
      (node (ref "J1") (pin "38") (pinfunction "MOSI1/BCM20_38") (pintype "bidirectional"))
    )
    (net (code "87") (name "unconnected-(J1-PWM0{slash}BCM12-Pad32)") (class "Default")
      (node (ref "J1") (pin "32") (pinfunction "PWM0/BCM12_32") (pintype "bidirectional"))
    )
    (net (code "88") (name "unconnected-(J1-SCK1{slash}BCM21-Pad40)") (class "Default")
      (node (ref "J1") (pin "40") (pinfunction "SCK1/BCM21_40") (pintype "bidirectional"))
    )
    (net (code "89") (name "unconnected-(J1-SD_CMD{slash}BCM23-Pad16)") (class "Default")
      (node (ref "J1") (pin "16") (pinfunction "SD_CMD/BCM23_16") (pintype "bidirectional"))
    )
    (net (code "90") (name "unconnected-(J1-SD_DAT0{slash}BCM24-Pad18)") (class "Default")
      (node (ref "J1") (pin "18") (pinfunction "SD_DAT0/BCM24_18") (pintype "bidirectional"))
    )
    (net (code "91") (name "unconnected-(J1-SD_DAT1{slash}BCM25-Pad22)") (class "Default")
      (node (ref "J1") (pin "22") (pinfunction "SD_DAT1/BCM25_22") (pintype "bidirectional"))
    )
    (net (code "92") (name "unconnected-(J1-~{CE00}{slash}BCM8-Pad24)") (class "Default")
      (node (ref "J1") (pin "24") (pinfunction "~{CE00}/BCM8_24") (pintype "bidirectional"))
    )
    (net (code "93") (name "unconnected-(J1-~{CE01}{slash}BCM7-Pad26)") (class "Default")
      (node (ref "J1") (pin "26") (pinfunction "~{CE01}/BCM7_26") (pintype "bidirectional"))
    )
    (net (code "94") (name "unconnected-(J3-Pad1)") (class "Default")
      (node (ref "J3") (pin "1") (pinfunction "1_1") (pintype "passive"))
    )
    (net (code "95") (name "unconnected-(J3-Pad2)") (class "Default")
      (node (ref "J3") (pin "2") (pinfunction "2_2") (pintype "passive"))
    )
    (net (code "96") (name "unconnected-(J3-Pad5)") (class "Default")
      (node (ref "J3") (pin "5") (pinfunction "5_5") (pintype "passive"))
    )
    (net (code "97") (name "unconnected-(J3-Pad6)") (class "Default")
      (node (ref "J3") (pin "6") (pinfunction "6_6") (pintype "passive"))
    )
    (net (code "98") (name "unconnected-(J3-Pad7)") (class "Default")
      (node (ref "J3") (pin "7") (pinfunction "7_7") (pintype "passive"))
    )
    (net (code "99") (name "unconnected-(J3-Pad8)") (class "Default")
      (node (ref "J3") (pin "8") (pinfunction "8_8") (pintype "passive"))
    )
    (net (code "100") (name "unconnected-(J3-Pad9)") (class "Default")
      (node (ref "J3") (pin "9") (pinfunction "9_9") (pintype "passive"))
    )
    (net (code "101") (name "unconnected-(J3-Pad10)") (class "Default")
      (node (ref "J3") (pin "10") (pinfunction "10_10") (pintype "passive"))
    )
    (net (code "102") (name "unconnected-(J5-Pad3)") (class "Default")
      (node (ref "J5") (pin "3") (pinfunction "3_3") (pintype "passive"))
    )
    (net (code "103") (name "unconnected-(J5-Pad5)") (class "Default")
      (node (ref "J5") (pin "5") (pinfunction "5_5") (pintype "passive"))
    )
    (net (code "104") (name "unconnected-(J5-Pad6)") (class "Default")
      (node (ref "J5") (pin "6") (pinfunction "6_6") (pintype "passive"))
    )
    (net (code "105") (name "unconnected-(J5-Pad7)") (class "Default")
      (node (ref "J5") (pin "7") (pinfunction "7_7") (pintype "passive"))
    )
    (net (code "106") (name "unconnected-(J5-Pad9)") (class "Default")
      (node (ref "J5") (pin "9") (pinfunction "9_9") (pintype "passive"))
    )
    (net (code "107") (name "unconnected-(J5-Pad10)") (class "Default")
      (node (ref "J5") (pin "10") (pinfunction "10_10") (pintype "passive"))
    )
    (net (code "108") (name "unconnected-(J6-Pad1)") (class "Default")
      (node (ref "J6") (pin "1") (pinfunction "1_1") (pintype "passive"))
    )
    (net (code "109") (name "unconnected-(J6-Pad2)") (class "Default")
      (node (ref "J6") (pin "2") (pinfunction "2_2") (pintype "passive"))
    )
    (net (code "110") (name "unconnected-(J6-Pad3)") (class "Default")
      (node (ref "J6") (pin "3") (pinfunction "3_3") (pintype "passive"))
    )
    (net (code "111") (name "unconnected-(J6-Pad4)") (class "Default")
      (node (ref "J6") (pin "4") (pinfunction "4_4") (pintype "passive"))
    )
    (net (code "112") (name "unconnected-(J6-Pad5)") (class "Default")
      (node (ref "J6") (pin "5") (pinfunction "5_5") (pintype "passive"))
    )
    (net (code "113") (name "unconnected-(J6-Pad6)") (class "Default")
      (node (ref "J6") (pin "6") (pinfunction "6_6") (pintype "passive"))
    )
    (net (code "114") (name "unconnected-(J6-Pad7)") (class "Default")
      (node (ref "J6") (pin "7") (pinfunction "7_7") (pintype "passive"))
    )
    (net (code "115") (name "unconnected-(J6-Pad8)") (class "Default")
      (node (ref "J6") (pin "8") (pinfunction "8_8") (pintype "passive"))
    )
    (net (code "116") (name "unconnected-(J6-Pad10)") (class "Default")
      (node (ref "J6") (pin "10") (pinfunction "10_10") (pintype "passive"))
    )
    (net (code "117") (name "unconnected-(J7-Pad5)") (class "Default")
      (node (ref "J7") (pin "5") (pinfunction "5_5") (pintype "passive"))
    )
    (net (code "118") (name "unconnected-(J7-Pad8)") (class "Default")
      (node (ref "J7") (pin "8") (pinfunction "8_8") (pintype "passive"))
    )
    (net (code "119") (name "unconnected-(J8-Pad5)") (class "Default")
      (node (ref "J8") (pin "5") (pinfunction "5_5") (pintype "passive"))
    )
    (net (code "120") (name "unconnected-(U7-(A7{slash}T3{slash}MOSI1)PE3-Pad22)") (class "Default")
      (node (ref "U7") (pin "22") (pinfunction "(A7/T3/MOSI1)PE3_22") (pintype "bidirectional"))
    )
    (net (code "121") (name "unconnected-(U7-(ICP3{slash}~{SS1})PE2-Pad19)") (class "Default")
      (node (ref "U7") (pin "19") (pinfunction "(ICP3/~{SS1})PE2_19") (pintype "bidirectional"))
    )
  )
)
